# light.net
KiCad netlist of a schematic drawn in Altium Designer
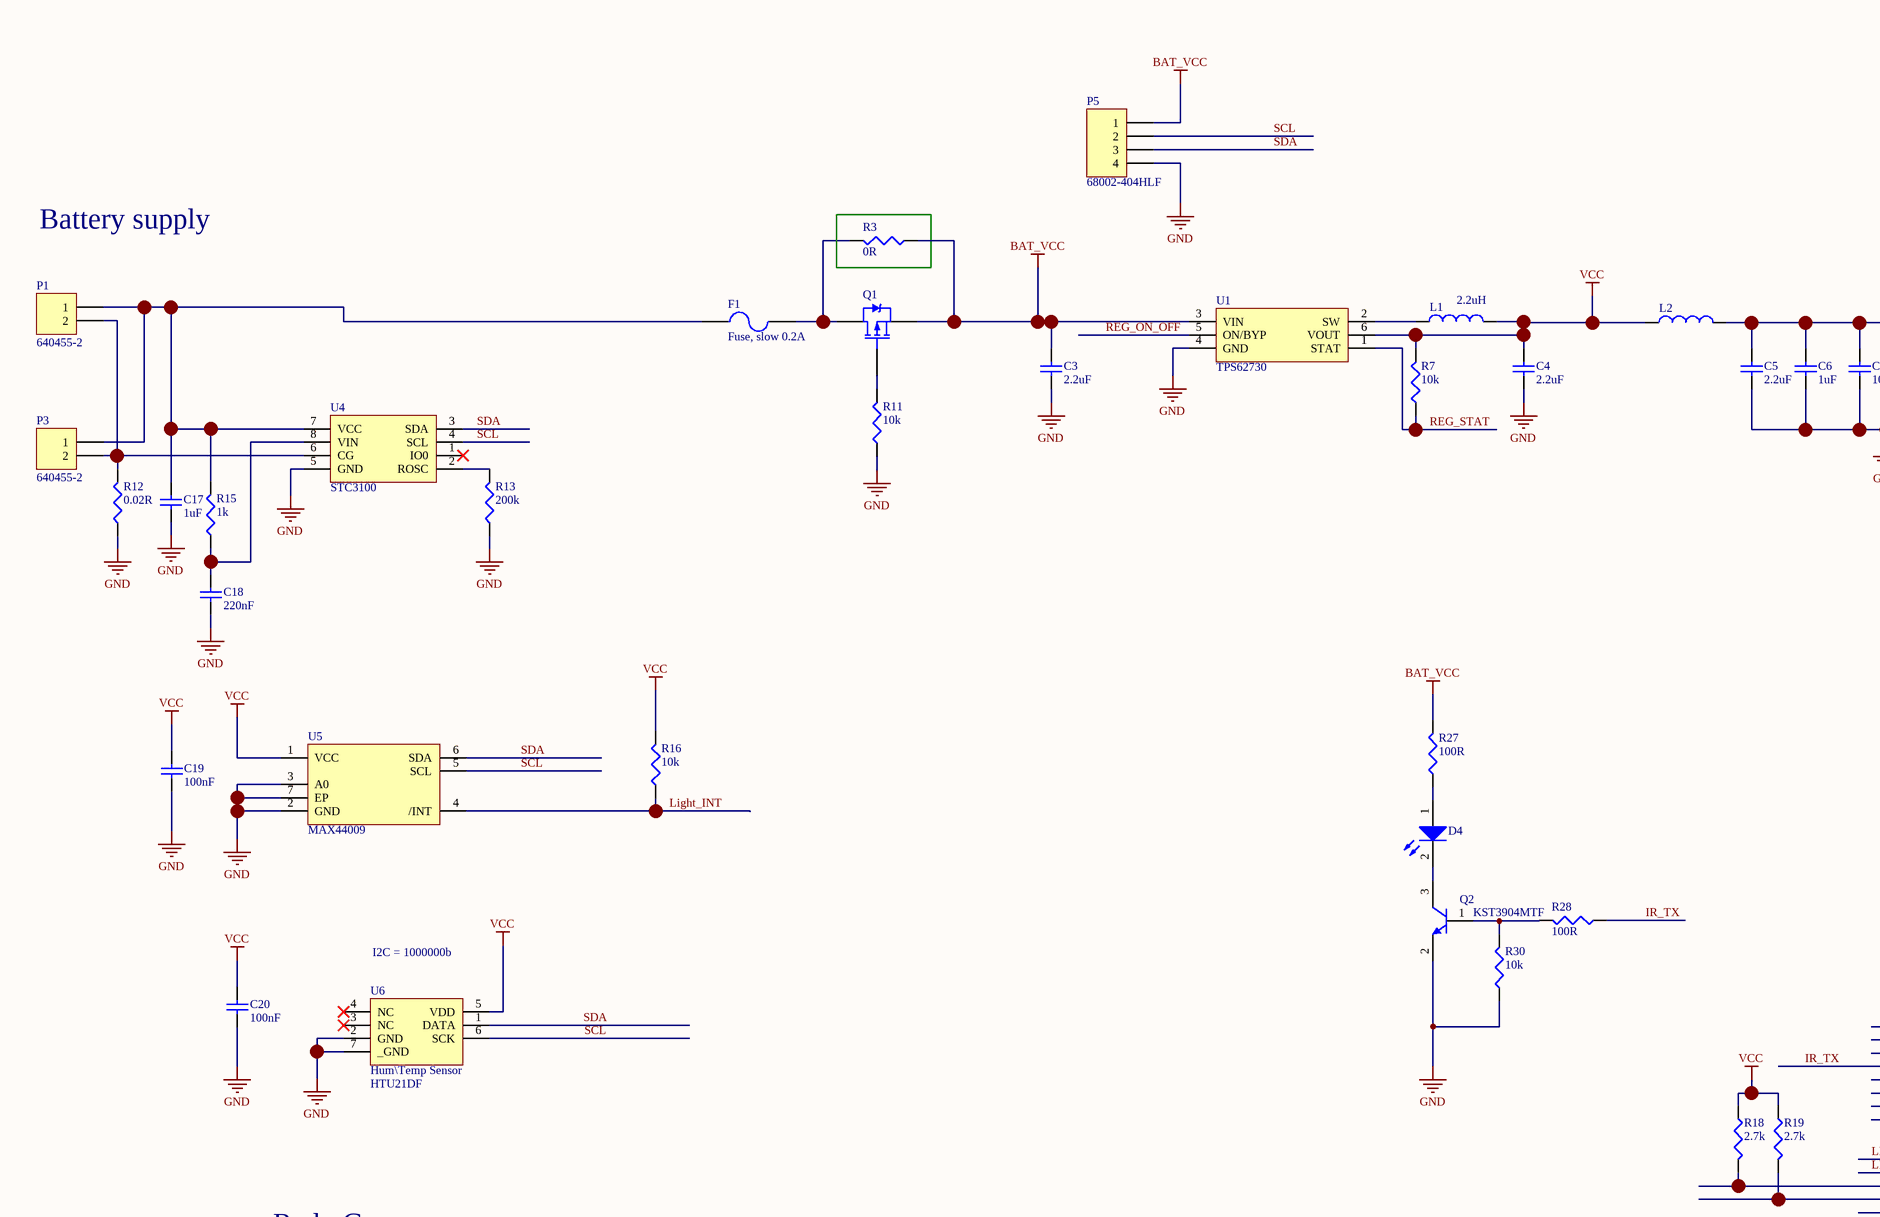
[diagram p0: light.SchDoc, top left]
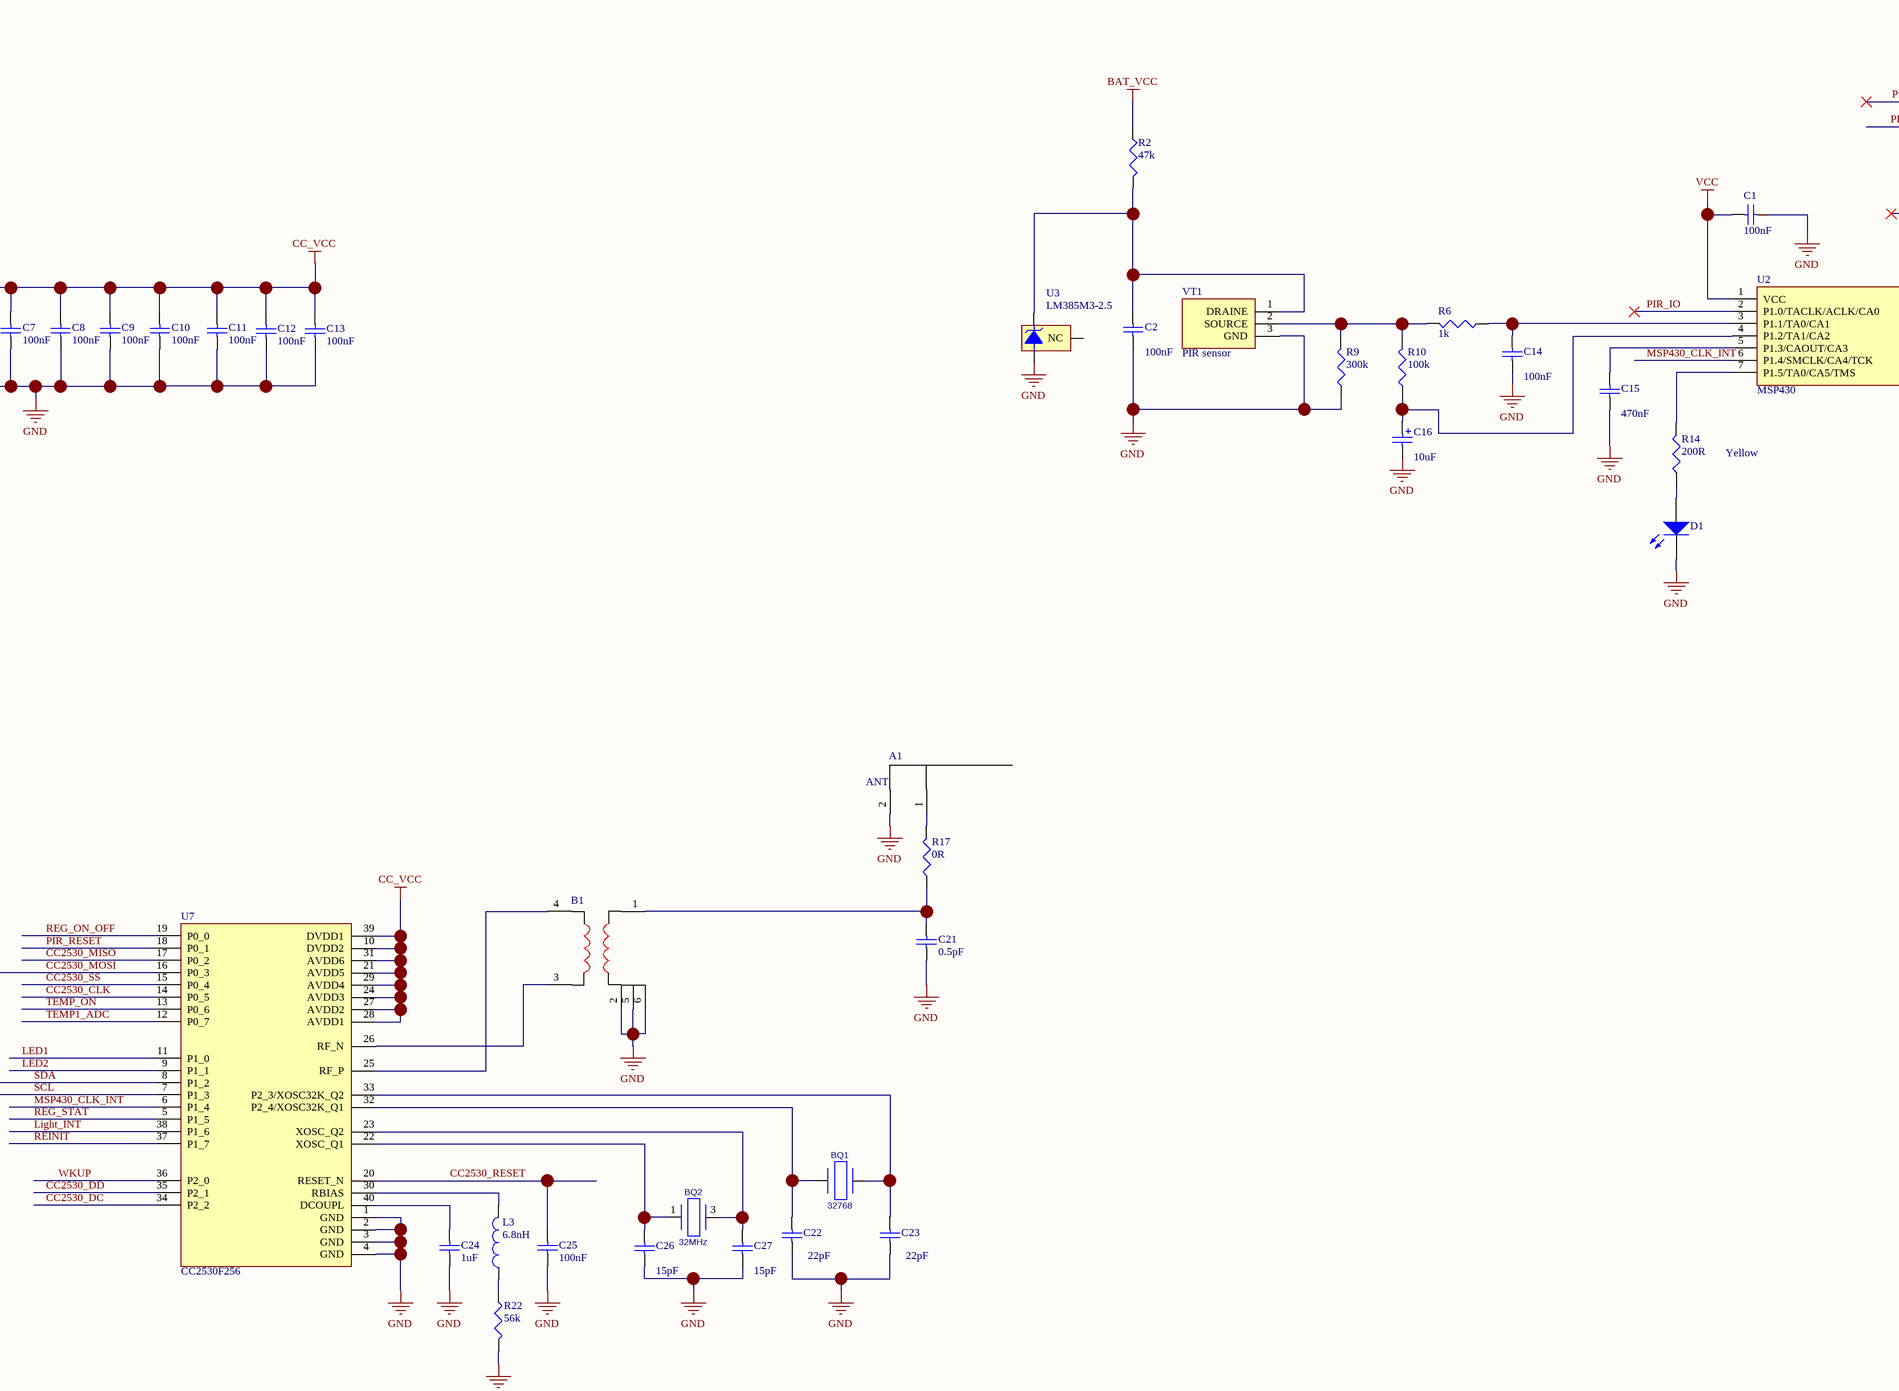
[diagram p1: light.SchDoc, top middle]
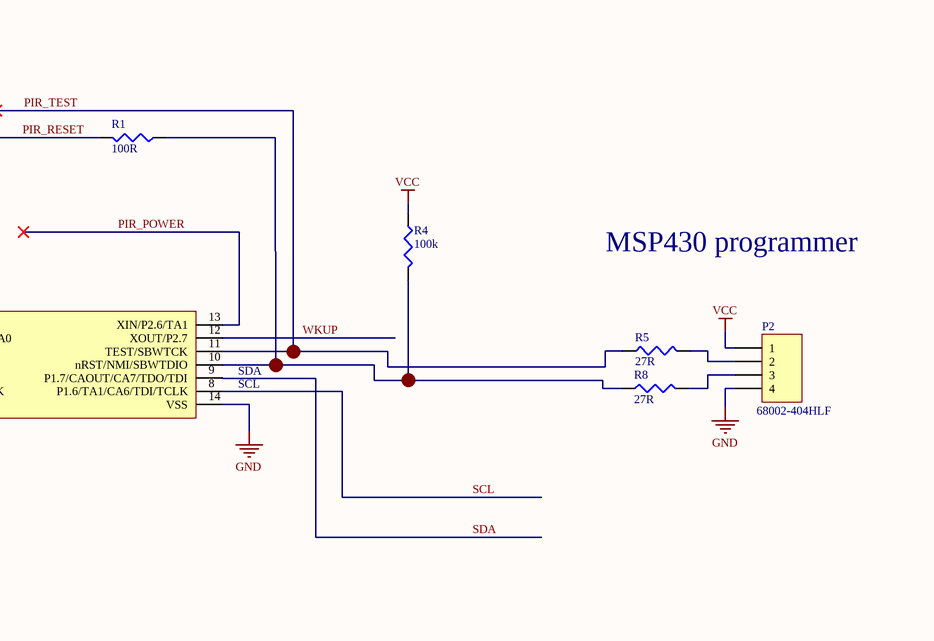
[diagram p2: light.SchDoc, top right]
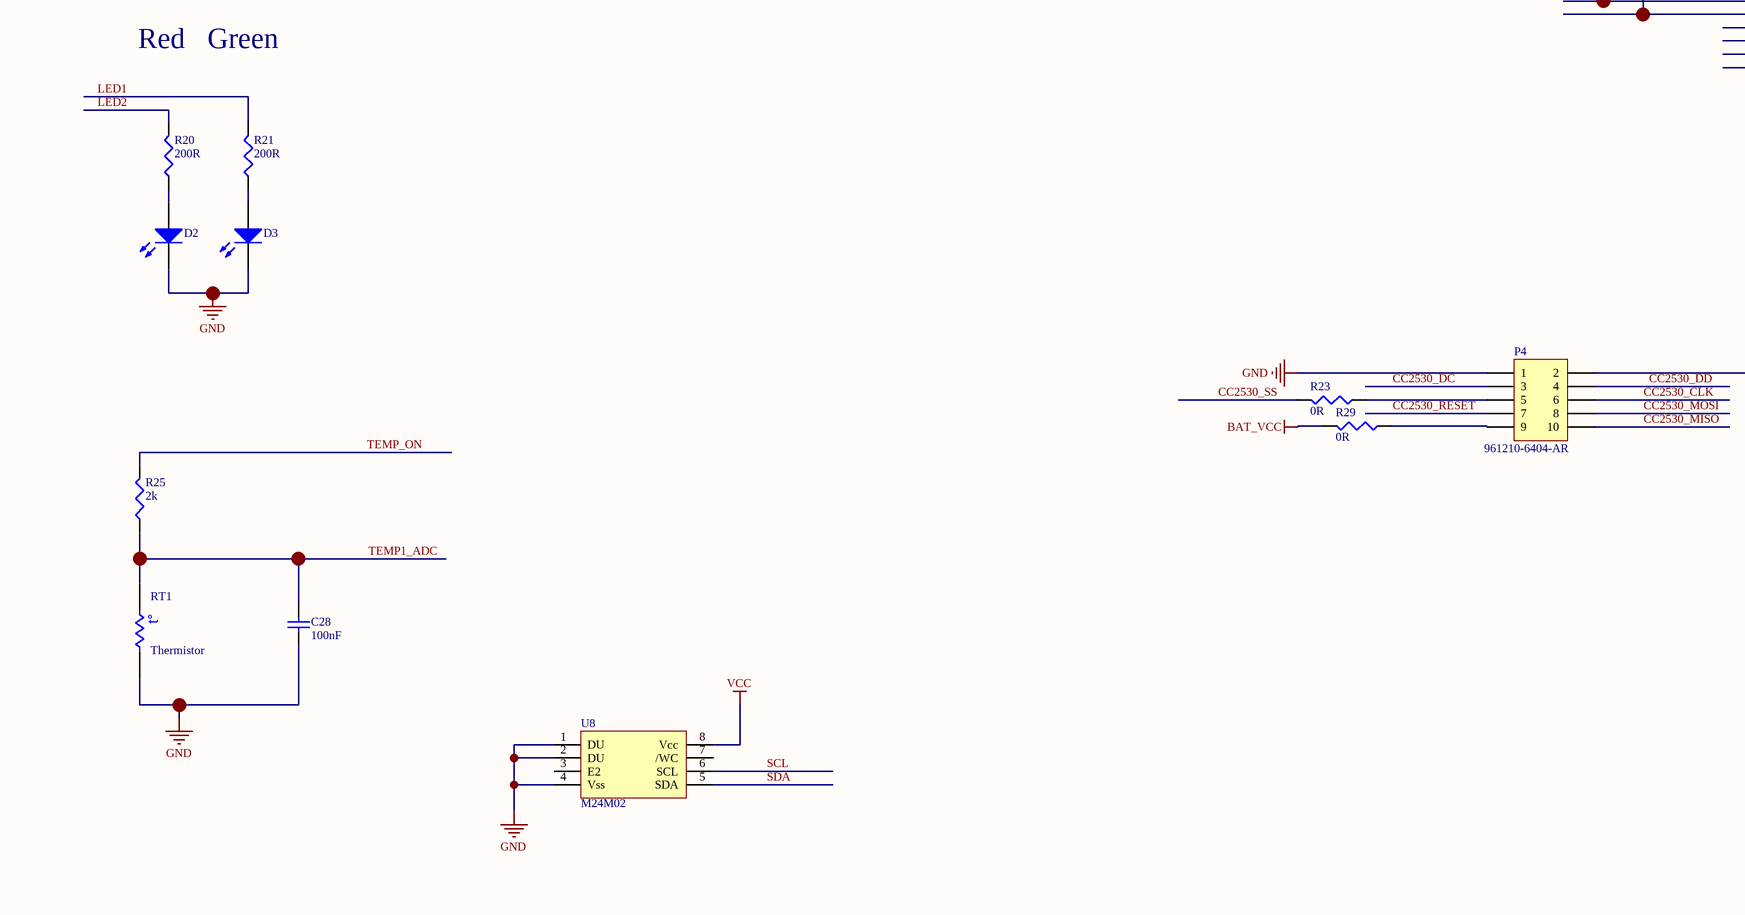
[diagram p3: light.SchDoc, bottom left]
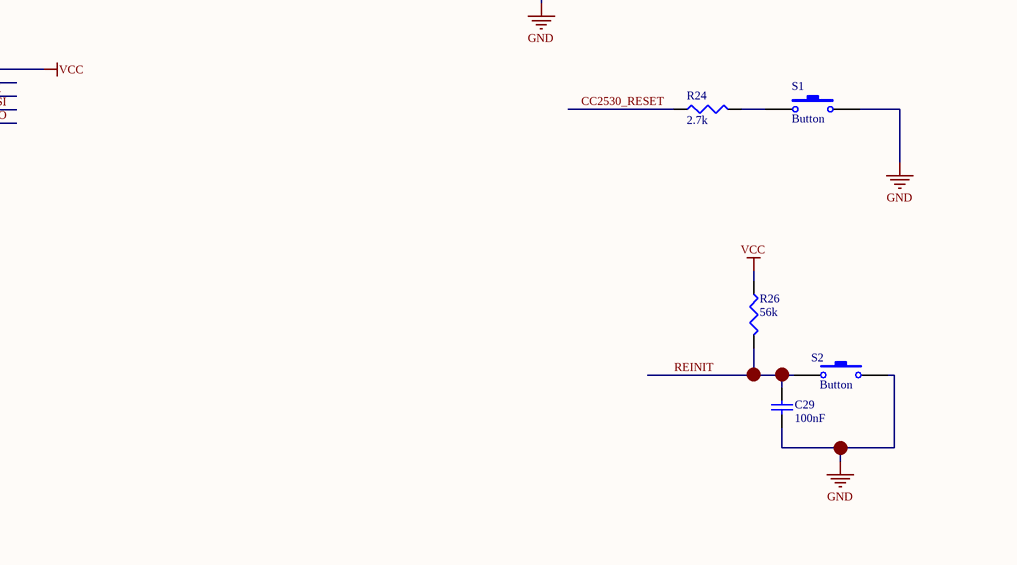
[diagram p4: light.SchDoc, bottom middle]
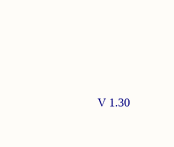
[diagram p5: light.SchDoc, bottom right]

(export (version "E")
  (design (tool "Eeschema 10.0.6"))
  (components
    (comp (ref "A1")
      (value "ANT")
      (footprint "F ant")
      (description "Inverted-F Antenna")
      (fields (field (name "MANUFACTURER PART NUMBER") "PCB ANT"))
      (libsource (lib "CC25xx") (part "ANT"))
    )
    (comp (ref "B1")
      (value "BALUN")
      (footprint "2450BM15A0002")
      (description "BALUN JTI MATCHED ZIGBEE")
      (fields
        (field (name "MANUFACTURER PART NUMBER") "2450BM15A0002E")
        (field (name "MANUFACTURER") "Johanson Technology Inc")
      )
      (libsource (lib "CC25xx") (part "BALUN"))
    )
    (comp (ref "BQ1")
      (value "32768")
      (footprint "FC-12M")
      (description "CRYSTAL 32.768KHZ 12.5PF SMD")
      (fields
        (field (name "MANUFACTURER PART NUMBER") "FC-12M 32.7680KA-A3")
        (field (name "MANUFACTURER") "EPSON")
      )
      (libsource (lib "*") (part "6LC{colon}308C"))
    )
    (comp (ref "BQ2")
      (value "32MHz")
      (footprint "403C11A32M00000")
      (description "CRYSTAL 32MHZ 10PF SMD")
      (fields
        (field (name "MANUFACTURER PART NUMBER") "403C11A32M00000")
        (field (name "MANUFACTURER") "CTS-Frequency Controls")
      )
      (libsource (lib "*") (part "HC-49SMD"))
    )
    (comp (ref "C1")
      (value "100nF")
      (footprint "0402")
      (description "CAP CER 0.1UF 10V 20% X5R 0402")
      (fields
        (field (name "MANUFACTURER PART NUMBER") "CL05A104MP5NNNC")
        (field (name "MANUFACTURER") "Samsung Electro-Mechanics America, Inc")
      )
      (libsource (lib "Miscellaneous Devices") (part "Cap"))
    )
    (comp (ref "C2")
      (value "100nF")
      (footprint "6-0805_L")
      (description "CAP FILM 0.1UF 16VDC 0805")
      (fields
        (field (name "MANUFACTURER PART NUMBER") "ECP-U1C104MA5")
        (field (name "MANUFACTURER") "Panasonic Electronic Components")
      )
      (libsource (lib "Miscellaneous Devices") (part "Cap"))
    )
    (comp (ref "C3")
      (value "2.2uF")
      (footprint "0402")
      (description "CAP CER 2.2UF 6.3V 20% X5R 0402")
      (fields
        (field (name "MANUFACTURER PART NUMBER") "CL05A225MQ5NNNC")
        (field (name "MANUFACTURER") "Samsung Electro-Mechanics America, Inc")
      )
      (libsource (lib "Miscellaneous Devices") (part "Cap"))
    )
    (comp (ref "C4")
      (value "2.2uF")
      (footprint "0402")
      (description "CAP CER 2.2UF 6.3V 20% X5R 0402")
      (fields
        (field (name "MANUFACTURER PART NUMBER") "CL05A225MQ5NNNC")
        (field (name "MANUFACTURER") "Samsung Electro-Mechanics America, Inc")
      )
      (libsource (lib "Miscellaneous Devices") (part "Cap"))
    )
    (comp (ref "C5")
      (value "2.2uF")
      (footprint "0402")
      (description "CAP CER 2.2UF 6.3V 20% X5R 0402")
      (fields
        (field (name "MANUFACTURER PART NUMBER") "CL05A225MQ5NNNC")
        (field (name "MANUFACTURER") "Samsung Electro-Mechanics America, Inc")
      )
      (libsource (lib "Miscellaneous Devices") (part "Cap"))
    )
    (comp (ref "C6")
      (value "1uF")
      (footprint "0402")
      (description "CAP CER 1UF 6.3V 10% X5R 0402")
      (fields
        (field (name "MANUFACTURER PART NUMBER") "GRM155R60J105KE19D")
        (field (name "MANUFACTURER") "Murata Electronics North America")
      )
      (libsource (lib "Miscellaneous Devices") (part "Cap"))
    )
    (comp (ref "C7")
      (value "100nF")
      (footprint "0402")
      (description "CAP CER 0.1UF 10V 20% X5R 0402")
      (fields
        (field (name "MANUFACTURER PART NUMBER") "CL05A104MP5NNNC")
        (field (name "MANUFACTURER") "Samsung Electro-Mechanics America, Inc")
      )
      (libsource (lib "Miscellaneous Devices") (part "Cap"))
    )
    (comp (ref "C8")
      (value "100nF")
      (footprint "0402")
      (description "CAP CER 0.1UF 10V 20% X5R 0402")
      (fields
        (field (name "MANUFACTURER PART NUMBER") "CL05A104MP5NNNC")
        (field (name "MANUFACTURER") "Samsung Electro-Mechanics America, Inc")
      )
      (libsource (lib "Miscellaneous Devices") (part "Cap"))
    )
    (comp (ref "C9")
      (value "100nF")
      (footprint "0402")
      (description "CAP CER 0.1UF 10V 20% X5R 0402")
      (fields
        (field (name "MANUFACTURER PART NUMBER") "CL05A104MP5NNNC")
        (field (name "MANUFACTURER") "Samsung Electro-Mechanics America, Inc")
      )
      (libsource (lib "Miscellaneous Devices") (part "Cap"))
    )
    (comp (ref "C10")
      (value "100nF")
      (footprint "0402")
      (description "CAP CER 0.1UF 10V 20% X5R 0402")
      (fields
        (field (name "MANUFACTURER PART NUMBER") "CL05A104MP5NNNC")
        (field (name "MANUFACTURER") "Samsung Electro-Mechanics America, Inc")
      )
      (libsource (lib "Miscellaneous Devices") (part "Cap"))
    )
    (comp (ref "C11")
      (value "100nF")
      (footprint "0402")
      (description "CAP CER 0.1UF 10V 20% X5R 0402")
      (fields
        (field (name "MANUFACTURER PART NUMBER") "CL05A104MP5NNNC")
        (field (name "MANUFACTURER") "Samsung Electro-Mechanics America, Inc")
      )
      (libsource (lib "Miscellaneous Devices") (part "Cap"))
    )
    (comp (ref "C12")
      (value "100nF")
      (footprint "0402")
      (description "CAP CER 0.1UF 10V 20% X5R 0402")
      (fields
        (field (name "MANUFACTURER PART NUMBER") "CL05A104MP5NNNC")
        (field (name "MANUFACTURER") "Samsung Electro-Mechanics America, Inc")
      )
      (libsource (lib "Miscellaneous Devices") (part "Cap"))
    )
    (comp (ref "C13")
      (value "100nF")
      (footprint "0402")
      (description "CAP CER 0.1UF 10V 20% X5R 0402")
      (fields
        (field (name "MANUFACTURER PART NUMBER") "CL05A104MP5NNNC")
        (field (name "MANUFACTURER") "Samsung Electro-Mechanics America, Inc")
      )
      (libsource (lib "Miscellaneous Devices") (part "Cap"))
    )
    (comp (ref "C14")
      (value "100nF")
      (footprint "6-0805_L")
      (description "CAP FILM 0.1UF 16VDC 0805")
      (fields
        (field (name "MANUFACTURER PART NUMBER") "ECP-U1C104MA5")
        (field (name "MANUFACTURER") "Panasonic Electronic Components")
      )
      (libsource (lib "Miscellaneous Devices") (part "Cap"))
    )
    (comp (ref "C15")
      (value "470nF")
      (footprint "1206")
      (description "CAP FILM 0.47UF 16VDC 1206")
      (fields
        (field (name "MANUFACTURER PART NUMBER") "ECP-U1C474MA5")
        (field (name "MANUFACTURER") "Panasonic Electronic Components")
      )
      (libsource (lib "Miscellaneous Devices") (part "Cap"))
    )
    (comp (ref "C16")
      (value "10uF")
      (footprint "0603")
      (description "CAP CER 10UF 6.3V 20% X5R 0603")
      (fields
        (field (name "MANUFACTURER PART NUMBER") "GRM188R60J106ME47D")
        (field (name "MANUFACTURER") "Murata Electronics North America")
      )
      (libsource (lib "Miscellaneous Devices") (part "Cap Pol2"))
    )
    (comp (ref "C17")
      (value "1uF")
      (footprint "0402")
      (description "CAP CER 1UF 6.3V 10% X5R 0402")
      (fields
        (field (name "MANUFACTURER PART NUMBER") "GRM155R60J105KE19D")
        (field (name "MANUFACTURER") "Murata Electronics North America")
      )
      (libsource (lib "Miscellaneous Devices") (part "Cap"))
    )
    (comp (ref "C18")
      (value "220nF")
      (footprint "0402")
      (description "CAP CER 0.22UF 10V 10% X5R 0402")
      (fields
        (field (name "MANUFACTURER PART NUMBER") "CL05A224KP5NNNC")
        (field (name "MANUFACTURER") "Samsung Electro-Mechanics America, Inc")
      )
      (libsource (lib "Miscellaneous Devices") (part "Cap"))
    )
    (comp (ref "C19")
      (value "100nF")
      (footprint "0402")
      (description "CAP CER 0.1UF 10V 20% X5R 0402")
      (fields
        (field (name "MANUFACTURER PART NUMBER") "CL05A104MP5NNNC")
        (field (name "MANUFACTURER") "Samsung Electro-Mechanics America, Inc")
      )
      (libsource (lib "Miscellaneous Devices") (part "Cap"))
    )
    (comp (ref "C20")
      (value "100nF")
      (footprint "0402")
      (description "CAP CER 0.1UF 10V 20% X5R 0402")
      (fields
        (field (name "MANUFACTURER PART NUMBER") "CL05A104MP5NNNC")
        (field (name "MANUFACTURER") "Samsung Electro-Mechanics America, Inc")
      )
      (libsource (lib "Miscellaneous Devices") (part "Cap"))
    )
    (comp (ref "C21")
      (value "0.5pF")
      (footprint "0402")
      (description "CAP CER 0.5PF 50V NP0 0402")
      (fields
        (field (name "MANUFACTURER PART NUMBER") "GRM1555C1HR50CA01D")
        (field (name "MANUFACTURER") "Murata Electronics North America")
      )
      (libsource (lib "Miscellaneous Devices") (part "Cap"))
    )
    (comp (ref "C22")
      (value "22pF")
      (footprint "0402")
      (description "CAP CER 22PF 50V 5% NP0 0402")
      (fields
        (field (name "MANUFACTURER PART NUMBER") "GRM1555C1H220JA01D")
        (field (name "MANUFACTURER") "Murata Electronics North America")
      )
      (libsource (lib "Miscellaneous Devices") (part "Cap"))
    )
    (comp (ref "C23")
      (value "22pF")
      (footprint "0402")
      (description "CAP CER 22PF 50V 5% NP0 0402")
      (fields
        (field (name "MANUFACTURER PART NUMBER") "GRM1555C1H220JA01D")
        (field (name "MANUFACTURER") "Murata Electronics North America")
      )
      (libsource (lib "Miscellaneous Devices") (part "Cap"))
    )
    (comp (ref "C24")
      (value "1uF")
      (footprint "0402")
      (description "CAP CER 1UF 6.3V 10% X5R 0402")
      (fields
        (field (name "MANUFACTURER PART NUMBER") "GRM155R60J105KE19D")
        (field (name "MANUFACTURER") "Murata Electronics North America")
      )
      (libsource (lib "Miscellaneous Devices") (part "Cap"))
    )
    (comp (ref "C25")
      (value "100nF")
      (footprint "0402")
      (description "CAP CER 0.1UF 10V 20% X5R 0402")
      (fields
        (field (name "MANUFACTURER PART NUMBER") "CL05A104MP5NNNC")
        (field (name "MANUFACTURER") "Samsung Electro-Mechanics America, Inc")
      )
      (libsource (lib "Miscellaneous Devices") (part "Cap"))
    )
    (comp (ref "C26")
      (value "15pF")
      (footprint "0402")
      (description "CAP CER 15PF 50V 5% NP0 0402")
      (fields
        (field (name "MANUFACTURER PART NUMBER") "GRM1555C1H150JA01D")
        (field (name "MANUFACTURER") "Murata Electronics North America")
      )
      (libsource (lib "Miscellaneous Devices") (part "Cap"))
    )
    (comp (ref "C27")
      (value "15pF")
      (footprint "0402")
      (description "CAP CER 15PF 50V 5% NP0 0402")
      (fields
        (field (name "MANUFACTURER PART NUMBER") "GRM1555C1H150JA01D")
        (field (name "MANUFACTURER") "Murata Electronics North America")
      )
      (libsource (lib "Miscellaneous Devices") (part "Cap"))
    )
    (comp (ref "C28")
      (value "100nF")
      (footprint "0402")
      (description "CAP CER 0.1UF 10V 20% X5R 0402")
      (fields
        (field (name "MANUFACTURER PART NUMBER") "CL05A104MP5NNNC")
        (field (name "MANUFACTURER") "Samsung Electro-Mechanics America, Inc")
      )
      (libsource (lib "Miscellaneous Devices") (part "Cap"))
    )
    (comp (ref "C29")
      (value "100nF")
      (footprint "0402")
      (description "CAP CER 0.1UF 10V 20% X5R 0402")
      (fields
        (field (name "MANUFACTURER PART NUMBER") "CL05A104MP5NNNC")
        (field (name "MANUFACTURER") "Samsung Electro-Mechanics America, Inc")
      )
      (libsource (lib "Miscellaneous Devices") (part "Cap"))
    )
    (comp (ref "D1")
      (value "Led")
      (footprint "LED0603")
      (description "LED YELLOW ROUND CLEAR SMD")
      (fields
        (field (name "MANUFACTURER PART NUMBER") "APTD1608SYCK")
        (field (name "MANUFACTURER") "Kingbright Company LLC")
      )
      (libsource (lib "Miscellaneous Devices") (part "LED0"))
    )
    (comp (ref "D2")
      (value "Led")
      (footprint "LED0603")
      (description "LED RED ROUND CLEAR SMD")
      (fields
        (field (name "MANUFACTURER PART NUMBER") "APTD1608SURCK")
        (field (name "MANUFACTURER") "Kingbright Company LLC")
      )
      (libsource (lib "Miscellaneous Devices") (part "LED0"))
    )
    (comp (ref "D3")
      (value "Led")
      (footprint "LED0603")
      (description "LED GREEN CLEAR THIN 0603 SMD")
      (fields
        (field (name "MANUFACTURER PART NUMBER") "LTST-C191KGKT")
        (field (name "MANUFACTURER") "Lite-On Inc")
      )
      (libsource (lib "Miscellaneous Devices") (part "LED0"))
    )
    (comp (ref "D4")
      (value "Led")
      (footprint "TSHF5410")
      (description "EMITTER IR 5MM HI EFF 940NM")
      (fields
        (field (name "MANUFACTURER PART NUMBER") "TSAL6400")
        (field (name "MANUFACTURER") "Vishay Semiconductor Opto Division")
      )
      (libsource (lib "") (part "LED0_1"))
    )
    (comp (ref "F1")
      (value "Fuse, slow 0.2A")
      (footprint "SF1206S0502")
      (description "FUSE .200A 125V FAST 1206")
      (fields
        (field (name "MANUFACTURER PART NUMBER") "0466.200NR")
        (field (name "MANUFACTURER") "Littelfuse Inc")
      )
      (libsource (lib "Miscellaneous Devices") (part "Fuse 2"))
    )
    (comp (ref "L1")
      (value "2.2uH")
      (footprint "6-0805_L")
      (description "INDUCTOR 2.2UH 0805")
      (fields
        (field (name "MANUFACTURER PART NUMBER") "LQM21PN2R2NGCD")
        (field (name "MANUFACTURER") "Murata Electronics North America")
      )
      (libsource (lib "Miscellaneous Devices") (part "Inductor"))
    )
    (comp (ref "L2")
      (value "Inductor")
      (footprint "0402")
      (description "FILTER CHIP 1000 OHM 250MA 0402")
      (fields
        (field (name "MANUFACTURER PART NUMBER") "BLM15HG102SN1D")
        (field (name "MANUFACTURER") "Murata Electronics North America")
      )
      (libsource (lib "Miscellaneous Devices") (part "Inductor"))
    )
    (comp (ref "L3")
      (value "6.8nH")
      (footprint "0402")
      (description "INDUCTOR 6.8NH 300MA 0402")
      (fields
        (field (name "MANUFACTURER PART NUMBER") "LQG15HS6N8J02D")
        (field (name "MANUFACTURER") "Murata Electronics North America")
      )
      (libsource (lib "Miscellaneous Devices") (part "Inductor"))
    )
    (comp (ref "P1")
      (value "Connector")
      (footprint "BAT_CON")
      (description "CONN HEADER VERT 2POS .100 TIN")
      (fields
        (field (name "MANUFACTURER PART NUMBER") "640455-2")
        (field (name "MANUFACTURER") "TE Connectivity")
      )
      (libsource (lib "Miscellaneous Connectors") (part "Header 2"))
    )
    (comp (ref "P2")
      (value "Header 4")
      (footprint "HDR1X4")
      (description "CONN HEADER 4POS .100 STR TIN")
      (fields (field (name "MANUFACTURER PART NUMBER") "68002-404HLF") (field (name "MANUFACTURER") "FCI"))
      (libsource (lib "") (part "Header 4_1"))
    )
    (comp (ref "P3")
      (value "Connector")
      (footprint "BAT_CON")
      (description "CONN HEADER VERT 2POS .100 TIN")
      (fields
        (field (name "MANUFACTURER PART NUMBER") "640455-2")
        (field (name "MANUFACTURER") "TE Connectivity")
      )
      (libsource (lib "Miscellaneous Connectors") (part "Header 2"))
    )
    (comp (ref "P4")
      (value "*")
      (footprint "HDR2X5")
      (description "CONN HEADER VERT DUAL 10POS GOLD")
      (fields (field (name "MANUFACTURER PART NUMBER") "961210-6404-AR") (field (name "MANUFACTURER") "3M"))
      (libsource (lib "Miscellaneous Connectors") (part "Header 5X2"))
    )
    (comp (ref "P5")
      (value "Header 4")
      (footprint "HDR1X4")
      (description "CONN HEADER 4POS .100 STR TIN")
      (fields (field (name "MANUFACTURER PART NUMBER") "68002-404HLF") (field (name "MANUFACTURER") "FCI"))
      (libsource (lib "Miscellaneous Connectors") (part "Header 4"))
    )
    (comp (ref "Q1")
      (value "IRLML6302GTRPBF")
      (footprint "SOT-23_N")
      (description "HEXFET Power MOSFET")
      (fields
        (field (name "MANUFACTURER") "International Rectifier")
        (field (name "PUBLISHER") "Altium Limited")
      )
      (libsource (lib "IR Discrete MOSFET - Power") (part "IRLML6302"))
    )
    (comp (ref "Q2")
      (value "KST3904MTF")
      (footprint "SOT-23_N")
      (description "TRANSISTOR NPN 40V 200MA SOT-23")
      (fields (field (name "MANUFACTURER") "Fairchild Semiconductor"))
      (libsource (lib "Miscellaneous Devices") (part "2N3904"))
    )
    (comp (ref "R1")
      (value "100R")
      (footprint "0402")
      (description "RES 100 OHM 1/10W 5% 0402 SMD")
      (fields
        (field (name "MANUFACTURER PART NUMBER") "ERJ-2GEJ101X")
        (field (name "MANUFACTURER") "Panasonic Electronic Components")
      )
      (libsource (lib "Miscellaneous Devices") (part "Res3"))
    )
    (comp (ref "R2")
      (value "47k")
      (footprint "0603")
      (description "RES 47K OHM 1/10W 5% 0603 SMD")
      (fields
        (field (name "MANUFACTURER PART NUMBER") "RC0603JR-0747KL")
        (field (name "MANUFACTURER") "Yageo")
      )
      (libsource (lib "Miscellaneous Devices") (part "Res3"))
    )
    (comp (ref "R3")
      (value "0R")
      (footprint "0402")
      (description "RES 0.0 OHM 1/10W JUMP 0402 SMD")
      (fields
        (field (name "MANUFACTURER PART NUMBER") "ERJ-2GE0R00X")
        (field (name "MANUFACTURER") "Panasonic Electronic Components")
      )
      (libsource (lib "Miscellaneous Devices") (part "Res3"))
    )
    (comp (ref "R4")
      (value "100k")
      (footprint "0603")
      (description "RES 100K OHM 1/10W 5% 0603 SMD")
      (fields
        (field (name "MANUFACTURER PART NUMBER") "RC0603JR-07100KL")
        (field (name "MANUFACTURER") "Yageo")
      )
      (libsource (lib "Miscellaneous Devices") (part "Res3"))
    )
    (comp (ref "R5")
      (value "27R")
      (footprint "0603")
      (description "RES 27 OHM 1/10W 5% 0603")
      (fields
        (field (name "MANUFACTURER PART NUMBER") "RC1608J270CS")
        (field (name "MANUFACTURER") "Samsung Electro-Mechanics America, Inc")
      )
      (libsource (lib "Miscellaneous Devices") (part "Res3"))
    )
    (comp (ref "R6")
      (value "1k")
      (footprint "0603")
      (description "RES 1.0K OHM 1/10W 5% 0603 SMD")
      (fields
        (field (name "MANUFACTURER PART NUMBER") "RC0603JR-071KL")
        (field (name "MANUFACTURER") "Yageo")
      )
      (libsource (lib "Miscellaneous Devices") (part "Res3"))
    )
    (comp (ref "R7")
      (value "10k")
      (footprint "0402")
      (description "RES 10K OHM 1/10W 5% 0402 SMD")
      (fields
        (field (name "MANUFACTURER PART NUMBER") "ERJ-2GEJ103X")
        (field (name "MANUFACTURER") "Panasonic Electronic Components")
      )
      (libsource (lib "Miscellaneous Devices") (part "Res3"))
    )
    (comp (ref "R8")
      (value "27R")
      (footprint "0603")
      (description "RES 27 OHM 1/10W 5% 0603")
      (fields
        (field (name "MANUFACTURER PART NUMBER") "RC1608J270CS")
        (field (name "MANUFACTURER") "Samsung Electro-Mechanics America, Inc")
      )
      (libsource (lib "Miscellaneous Devices") (part "Res3"))
    )
    (comp (ref "R9")
      (value "300k")
      (footprint "0603")
      (description "RES 300K OHM 1/10W 5% 0603 SMD")
      (fields
        (field (name "MANUFACTURER PART NUMBER") "RC0603JR-07300KL")
        (field (name "MANUFACTURER") "Yageo")
      )
      (libsource (lib "Miscellaneous Devices") (part "Res3"))
    )
    (comp (ref "R10")
      (value "100k")
      (footprint "0603")
      (description "RES 100K OHM 1/10W 5% 0603 SMD")
      (fields
        (field (name "MANUFACTURER PART NUMBER") "RC0603JR-07100KL")
        (field (name "MANUFACTURER") "Yageo")
      )
      (libsource (lib "Miscellaneous Devices") (part "Res3"))
    )
    (comp (ref "R11")
      (value "10k")
      (footprint "0402")
      (description "RES 10K OHM 1/10W 5% 0402 SMD")
      (fields
        (field (name "MANUFACTURER PART NUMBER") "ERJ-2GEJ103X")
        (field (name "MANUFACTURER") "Panasonic Electronic Components")
      )
      (libsource (lib "Miscellaneous Devices") (part "Res3"))
    )
    (comp (ref "R12")
      (value "0.02R")
      (footprint "0603")
      (description "RES 0.02 OHM 1/4W 1% 0603")
      (fields
        (field (name "MANUFACTURER PART NUMBER") "RU1608FR020CS")
        (field (name "MANUFACTURER") "Samsung Electro-Mechanics America, Inc")
      )
      (libsource (lib "Miscellaneous Devices") (part "Res3"))
    )
    (comp (ref "R13")
      (value "200k")
      (footprint "6-0805_L")
      (description "RES 200K OHM 1/8W .1% 0805 SMD")
      (fields
        (field (name "MANUFACTURER PART NUMBER") "ERA-6AEB204V")
        (field (name "MANUFACTURER") "Panasonic Electronic Components")
      )
      (libsource (lib "Miscellaneous Devices") (part "Res3"))
    )
    (comp (ref "R14")
      (value "200R")
      (footprint "0603")
      (description "RES 200 OHM 1/10W 5% 0603 SMD")
      (fields
        (field (name "MANUFACTURER PART NUMBER") "RC0603JR-07200RL")
        (field (name "MANUFACTURER") "Yageo")
      )
      (libsource (lib "Miscellaneous Devices") (part "Res3"))
    )
    (comp (ref "R15")
      (value "1k")
      (footprint "0402")
      (description "RES 1K OHM 1/10W 1% 0402 SMD")
      (fields
        (field (name "MANUFACTURER PART NUMBER") "ERJ-2RKF1001X")
        (field (name "MANUFACTURER") "Panasonic Electronic Components")
      )
      (libsource (lib "Miscellaneous Devices") (part "Res3"))
    )
    (comp (ref "R16")
      (value "10k")
      (footprint "0402")
      (description "RES 10K OHM 1/10W 5% 0402 SMD")
      (fields
        (field (name "MANUFACTURER PART NUMBER") "ERJ-2GEJ103X")
        (field (name "MANUFACTURER") "Panasonic Electronic Components")
      )
      (libsource (lib "Miscellaneous Devices") (part "Res3"))
    )
    (comp (ref "R17")
      (value "0R")
      (footprint "0402")
      (description "RES 0.0 OHM 1/10W JUMP 0402 SMD")
      (fields
        (field (name "MANUFACTURER PART NUMBER") "ERJ-2GE0R00X")
        (field (name "MANUFACTURER") "Panasonic Electronic Components")
      )
      (libsource (lib "Miscellaneous Devices") (part "Res3"))
    )
    (comp (ref "R18")
      (value "2.7k")
      (footprint "0402")
      (description "RES 2.7K OHM 1/10W 5% 0402 SMD")
      (fields
        (field (name "MANUFACTURER PART NUMBER") "ERJ-2GEJ272X")
        (field (name "MANUFACTURER") "Panasonic Electronic Components")
      )
      (libsource (lib "Miscellaneous Devices") (part "Res3"))
    )
    (comp (ref "R19")
      (value "2.7k")
      (footprint "0402")
      (description "RES 2.7K OHM 1/10W 5% 0402 SMD")
      (fields
        (field (name "MANUFACTURER PART NUMBER") "ERJ-2GEJ272X")
        (field (name "MANUFACTURER") "Panasonic Electronic Components")
      )
      (libsource (lib "Miscellaneous Devices") (part "Res3"))
    )
    (comp (ref "R20")
      (value "200R")
      (footprint "0603")
      (description "RES 200 OHM 1/10W 5% 0603 SMD")
      (fields
        (field (name "MANUFACTURER PART NUMBER") "RC0603JR-07200RL")
        (field (name "MANUFACTURER") "Yageo")
      )
      (libsource (lib "Miscellaneous Devices") (part "Res3"))
    )
    (comp (ref "R21")
      (value "200R")
      (footprint "0603")
      (description "RES 200 OHM 1/10W 5% 0603 SMD")
      (fields
        (field (name "MANUFACTURER PART NUMBER") "RC0603JR-07200RL")
        (field (name "MANUFACTURER") "Yageo")
      )
      (libsource (lib "Miscellaneous Devices") (part "Res3"))
    )
    (comp (ref "R22")
      (value "56k")
      (footprint "0402")
      (description "RES 56K OHM 1/10W 1% 0402 SMD")
      (fields
        (field (name "MANUFACTURER PART NUMBER") "ERJ-2RKF5602X")
        (field (name "MANUFACTURER") "Panasonic Electronic Components")
      )
      (libsource (lib "Miscellaneous Devices") (part "Res3"))
    )
    (comp (ref "R23")
      (value "0R")
      (footprint "0402")
      (description "RES 0.0 OHM 1/10W JUMP 0402 SMD")
      (fields
        (field (name "MANUFACTURER PART NUMBER") "ERJ-2GE0R00X")
        (field (name "MANUFACTURER") "Panasonic Electronic Components")
      )
      (libsource (lib "Miscellaneous Devices") (part "Res3"))
    )
    (comp (ref "R24")
      (value "2.7k")
      (footprint "0402")
      (description "RES 2.7K OHM 1/10W 5% 0402 SMD")
      (fields
        (field (name "MANUFACTURER PART NUMBER") "ERJ-2GEJ272X")
        (field (name "MANUFACTURER") "Panasonic Electronic Components")
      )
      (libsource (lib "Miscellaneous Devices") (part "Res3"))
    )
    (comp (ref "R25")
      (value "2k")
      (footprint "0603")
      (description "RES 2.0K OHM 1/10W 5% 0603 SMD")
      (fields
        (field (name "MANUFACTURER PART NUMBER") "RC0603JR-072KL")
        (field (name "MANUFACTURER") "Yageo")
      )
      (libsource (lib "Miscellaneous Devices") (part "Res3"))
    )
    (comp (ref "R26")
      (value "56k")
      (footprint "0402")
      (description "RES 56K OHM 1/10W 1% 0402 SMD")
      (fields
        (field (name "MANUFACTURER PART NUMBER") "ERJ-2RKF5602X")
        (field (name "MANUFACTURER") "Panasonic Electronic Components")
      )
      (libsource (lib "Miscellaneous Devices") (part "Res3"))
    )
    (comp (ref "R27")
      (value "100R")
      (footprint "0603")
      (description "RES 100 OHM 1/10W 5% 0603 SMD")
      (fields
        (field (name "MANUFACTURER PART NUMBER") "ERJ-3GEYJ101V")
        (field (name "MANUFACTURER") "Panasonic Electronic Components")
      )
      (libsource (lib "Miscellaneous Devices") (part "Res3"))
    )
    (comp (ref "R28")
      (value "100R")
      (footprint "0603")
      (description "RES 100 OHM 1/10W 5% 0603 SMD")
      (fields
        (field (name "MANUFACTURER PART NUMBER") "ERJ-3GEYJ101V")
        (field (name "MANUFACTURER") "Panasonic Electronic Components")
      )
      (libsource (lib "Miscellaneous Devices") (part "Res3"))
    )
    (comp (ref "R29")
      (value "0R")
      (footprint "0402")
      (description "RES 0.0 OHM 1/10W JUMP 0402 SMD")
      (fields
        (field (name "MANUFACTURER PART NUMBER") "ERJ-2GE0R00X")
        (field (name "MANUFACTURER") "Panasonic Electronic Components")
      )
      (libsource (lib "Miscellaneous Devices") (part "Res3"))
    )
    (comp (ref "R30")
      (value "10k")
      (footprint "0402")
      (description "RES 10K OHM 1/10W 5% 0402 SMD")
      (fields
        (field (name "MANUFACTURER PART NUMBER") "ERJ-2GEJ103X")
        (field (name "MANUFACTURER") "Panasonic Electronic Components")
      )
      (libsource (lib "Miscellaneous Devices") (part "Res3"))
    )
    (comp (ref "RT1")
      (value "Thermistor")
      (footprint "0603")
      (description "THERMISTOR NTC 1K OHM 5% 0603")
      (fields
        (field (name "MANUFACTURER PART NUMBER") "ERT-J1VT102J")
        (field (name "MANUFACTURER") "Panasonic Electronic Components")
      )
      (libsource (lib "Miscellaneous Devices") (part "Res Thermal"))
    )
    (comp (ref "S1")
      (value "Button")
      (footprint "B3U-3000P")
      (description "SWITCH TACTILE")
      (fields
        (field (name "MANUFACTURER PART NUMBER") "B3U-1000P")
        (field (name "MANUFACTURER") "Omron Electronics Inc-EMC Div")
      )
      (libsource (lib "Miscellaneous Devices") (part "SW-PB"))
    )
    (comp (ref "S2")
      (value "Button")
      (footprint "TL3330")
      (description "SWITCH TACTILE SPST-NO 0.05A 12V")
      (fields
        (field (name "MANUFACTURER PART NUMBER") "TL3330AF260QG")
        (field (name "MANUFACTURER") "E-Switch")
      )
      (libsource (lib "Miscellaneous Devices") (part "SW-PB"))
    )
    (comp (ref "U1")
      (value "TPS62730")
      (footprint "6SON")
      (description "IC DCDC CONV STP-DN SYNC LP 6SON")
      (fields
        (field (name "MANUFACTURER PART NUMBER") "TPS62730DRYT")
        (field (name "MANUFACTURER") "Texas Instruments")
      )
      (libsource (lib "thermostat_main") (part "TPS62730"))
    )
    (comp (ref "U2")
      (value "MSP430")
      (footprint "TSOP14")
      (description "MIXED SIGNAL MICROCONTROLLER")
      (fields
        (field (name "MANUFACTURER PART NUMBER") "MSP430F2013IPW")
        (field (name "MANUFACTURER") "Texas Instruments")
      )
      (libsource (lib "msp") (part "MSP430F20x3"))
    )
    (comp (ref "U3")
      (value "LM385M3-2.5")
      (footprint "SOT23")
      (description "Micropower Voltage Reference Diode, 3-pin SOT-23")
      (fields
        (field (name "MANUFACTURER") "National Semiconductor")
        (field (name "MANUFACTURER PART NUMBER") "LM385M3-2.5/NOPB")
        (field (name "PUBLISHER") "Altium Limited")
      )
      (libsource (lib "NSC Voltage Reference") (part "LM385M3-2.5"))
    )
    (comp (ref "U4")
      (value "STC3100")
      (footprint "DFN8")
      (description "IC BATTERY MON W/GAUGE 8-DFN")
      (fields
        (field (name "MANUFACTURER PART NUMBER") "STC3100IQT")
        (field (name "MANUFACTURER") "STMicroelectronics")
      )
      (libsource (lib "CC25xx") (part "STC3100"))
    )
    (comp (ref "U5")
      (value "MAX44009")
      (footprint "QFN127P600-8N")
      (description "SENSOR AMBIENT LIGHT 6UTDFN")
      (fields
        (field (name "MANUFACTURER PART NUMBER") "MAX44009EDT+T")
        (field (name "MANUFACTURER") "Maxim Integrated")
      )
      (libsource (lib "thermostat_main") (part "MAX44009"))
    )
    (comp (ref "U6")
      (value "Hu~{m}Temp Sensor")
      (footprint "QFN6")
      (description "Miniature Relative Humidity and Temperature Sensor")
      (fields
        (field (name "MANUFACTURER PART NUMBER") "HTU21DF")
        (field (name "MANUFACTURER") "Measurement Specialties")
      )
      (libsource (lib "HTU21D") (part "HTU21D"))
    )
    (comp (ref "U7")
      (value "CC2530F256")
      (footprint "QFN40")
      (description "IC SOC IEEE 802.15.4/ZIG 40VQFN")
      (fields
        (field (name "MANUFACTURER PART NUMBER") "CC2530F256RHAT")
        (field (name "MANUFACTURER") "Texas Instruments")
      )
      (libsource (lib "CC25xx") (part "CC2530F256"))
    )
    (comp (ref "U8")
      (value "M24M02")
      (footprint "SO8")
      (description "IC EEPROM 2MBIT 1MHZ 8SO")
      (fields
        (field (name "MANUFACTURER PART NUMBER") "M24M02-DRMN6TP")
        (field (name "MANUFACTURER") "STMicroelectronics")
      )
      (libsource (lib "CC25xx") (part "M24M02"))
    )
    (comp (ref "VT1")
      (value "PIR sensor")
      (footprint "TO5")
      (fields (field (name "MANUFACTURER PART NUMBER") "C174") (field (name "MANUFACTURER") "Kube"))
      (libsource (lib "Zilog") (part "PIR_Sensor"))
    )
  )
  (nets
    (net (code "1") (name "/CC2530_CLK") (class "Default")
      (node (ref "P4") (pin "6") (pinfunction "6_6") (pintype "passive"))
      (node (ref "U7") (pin "14") (pinfunction "P0_5_14") (pintype "passive"))
    )
    (net (code "2") (name "/CC2530_DC") (class "Default")
      (node (ref "P4") (pin "3") (pinfunction "3_3") (pintype "passive"))
      (node (ref "U7") (pin "34") (pinfunction "P2_2_34") (pintype "passive"))
    )
    (net (code "3") (name "/CC2530_DD") (class "Default")
      (node (ref "P4") (pin "4") (pinfunction "4_4") (pintype "passive"))
      (node (ref "U7") (pin "35") (pinfunction "P2_1_35") (pintype "passive"))
    )
    (net (code "4") (name "/CC2530_MISO") (class "Default")
      (node (ref "P4") (pin "10") (pinfunction "10_10") (pintype "passive"))
      (node (ref "U7") (pin "17") (pinfunction "P0_2_17") (pintype "passive"))
    )
    (net (code "5") (name "/CC2530_MOSI") (class "Default")
      (node (ref "P4") (pin "8") (pinfunction "8_8") (pintype "passive"))
      (node (ref "R28") (pin "2") (pinfunction "2_2") (pintype "passive"))
      (node (ref "U7") (pin "16") (pinfunction "P0_3_16") (pintype "passive"))
    )
    (net (code "6") (name "/CC2530_RESET") (class "Default")
      (node (ref "C25") (pin "1") (pinfunction "1_1") (pintype "passive"))
      (node (ref "P4") (pin "7") (pinfunction "7_7") (pintype "passive"))
      (node (ref "R24") (pin "2") (pinfunction "2_2") (pintype "passive"))
      (node (ref "U7") (pin "20") (pinfunction "RESET_N_20") (pintype "passive"))
    )
    (net (code "7") (name "/CC2530_SS") (class "Default")
      (node (ref "R23") (pin "2") (pinfunction "2_2") (pintype "passive"))
      (node (ref "U7") (pin "15") (pinfunction "P0_4_15") (pintype "passive"))
    )
    (net (code "8") (name "/LED1") (class "Default")
      (node (ref "R21") (pin "1") (pinfunction "1_1") (pintype "passive"))
      (node (ref "U7") (pin "11") (pinfunction "P1_0_11") (pintype "passive"))
    )
    (net (code "9") (name "/LED2") (class "Default")
      (node (ref "R20") (pin "1") (pinfunction "1_1") (pintype "passive"))
      (node (ref "U7") (pin "9") (pinfunction "P1_1_9") (pintype "passive"))
    )
    (net (code "10") (name "/Light_INT") (class "Default")
      (node (ref "R16") (pin "2") (pinfunction "2_2") (pintype "passive"))
      (node (ref "U5") (pin "4") (pinfunction "/INT_4") (pintype "passive"))
      (node (ref "U7") (pin "38") (pinfunction "P1_6_38") (pintype "passive"))
    )
    (net (code "11") (name "/MSP430_CLK_INT") (class "Default")
      (node (ref "U2") (pin "6") (pinfunction "P1.4/SMCLK/CA4/TCK_6") (pintype "passive"))
      (node (ref "U7") (pin "6") (pinfunction "P1_4_6") (pintype "passive"))
    )
    (net (code "12") (name "/PIR_IO") (class "Default")
      (node (ref "U2") (pin "2") (pinfunction "P1.0/TACLK/ACLK/CA0_2") (pintype "passive+no_connect"))
    )
    (net (code "13") (name "/PIR_POWER") (class "Default")
      (node (ref "U2") (pin "13") (pinfunction "XIN/P2.6/TA1_13") (pintype "passive+no_connect"))
    )
    (net (code "14") (name "/PIR_RESET") (class "Default")
      (node (ref "R1") (pin "2") (pinfunction "2_2") (pintype "passive"))
      (node (ref "U7") (pin "18") (pinfunction "P0_1_18") (pintype "passive"))
    )
    (net (code "15") (name "/PIR_TEST") (class "Default")
      (node (ref "R5") (pin "1") (pinfunction "1_1") (pintype "passive"))
      (node (ref "U2") (pin "11") (pinfunction "TEST/SBWTCK_11") (pintype "passive"))
    )
    (net (code "16") (name "/REG_ON_OFF") (class "Default")
      (node (ref "U1") (pin "5") (pinfunction "ON/BYP_5") (pintype "passive"))
      (node (ref "U7") (pin "19") (pinfunction "P0_0_19") (pintype "passive"))
    )
    (net (code "17") (name "/REG_STAT") (class "Default")
      (node (ref "R7") (pin "2") (pinfunction "2_2") (pintype "passive"))
      (node (ref "U1") (pin "1") (pinfunction "STAT_1") (pintype "passive"))
      (node (ref "U7") (pin "5") (pinfunction "P1_5_5") (pintype "passive"))
    )
    (net (code "18") (name "/REINIT") (class "Default")
      (node (ref "C29") (pin "1") (pinfunction "1_1") (pintype "passive"))
      (node (ref "R26") (pin "2") (pinfunction "2_2") (pintype "passive"))
      (node (ref "S2") (pin "1") (pinfunction "1_1") (pintype "passive"))
      (node (ref "U7") (pin "37") (pinfunction "P1_7_37") (pintype "passive"))
    )
    (net (code "19") (name "/SCL") (class "Default")
      (node (ref "P5") (pin "2") (pinfunction "2_2") (pintype "passive"))
      (node (ref "R19") (pin "1") (pinfunction "1_1") (pintype "passive"))
      (node (ref "U2") (pin "8") (pinfunction "P1.6/TA1/CA6/TDI/TCLK_8") (pintype "passive"))
      (node (ref "U4") (pin "4") (pinfunction "SCL_4") (pintype "passive"))
      (node (ref "U5") (pin "5") (pinfunction "SCL_5") (pintype "passive"))
      (node (ref "U6") (pin "6") (pinfunction "SCK_6") (pintype "passive"))
      (node (ref "U7") (pin "7") (pinfunction "P1_3_7") (pintype "passive"))
      (node (ref "U8") (pin "6") (pinfunction "SCL_6") (pintype "passive"))
    )
    (net (code "20") (name "/SDA") (class "Default")
      (node (ref "P5") (pin "3") (pinfunction "3_3") (pintype "passive"))
      (node (ref "R18") (pin "1") (pinfunction "1_1") (pintype "passive"))
      (node (ref "U2") (pin "9") (pinfunction "P1.7/CAOUT/CA7/TDO/TDI_9") (pintype "passive"))
      (node (ref "U4") (pin "3") (pinfunction "SDA_3") (pintype "passive"))
      (node (ref "U5") (pin "6") (pinfunction "SDA_6") (pintype "passive"))
      (node (ref "U6") (pin "1") (pinfunction "DATA_1") (pintype "passive"))
      (node (ref "U7") (pin "8") (pinfunction "P1_2_8") (pintype "passive"))
      (node (ref "U8") (pin "5") (pinfunction "SDA_5") (pintype "passive"))
    )
    (net (code "21") (name "/TEMP1_ADC") (class "Default")
      (node (ref "C28") (pin "1") (pinfunction "1_1") (pintype "passive"))
      (node (ref "R25") (pin "1") (pinfunction "1_1") (pintype "passive"))
      (node (ref "RT1") (pin "1") (pinfunction "1_1") (pintype "passive"))
      (node (ref "U7") (pin "12") (pinfunction "P0_7_12") (pintype "passive"))
    )
    (net (code "22") (name "/TEMP_ON") (class "Default")
      (node (ref "R25") (pin "2") (pinfunction "2_2") (pintype "passive"))
      (node (ref "U7") (pin "13") (pinfunction "P0_6_13") (pintype "passive"))
    )
    (net (code "23") (name "/WKUP") (class "Default")
      (node (ref "U2") (pin "12") (pinfunction "XOUT/P2.7_12") (pintype "passive"))
      (node (ref "U7") (pin "36") (pinfunction "P2_0_36") (pintype "passive"))
    )
    (net (code "24") (name "BAT_VCC") (class "Default")
      (node (ref "C3") (pin "1") (pinfunction "1_1") (pintype "passive"))
      (node (ref "P5") (pin "1") (pinfunction "1_1") (pintype "passive"))
      (node (ref "Q1") (pin "2") (pinfunction "S_2") (pintype "passive"))
      (node (ref "R2") (pin "2") (pinfunction "2_2") (pintype "passive"))
      (node (ref "R27") (pin "1") (pinfunction "1_1") (pintype "passive"))
      (node (ref "R29") (pin "2") (pinfunction "2_2") (pintype "passive"))
      (node (ref "R3") (pin "1") (pinfunction "1_1") (pintype "passive"))
      (node (ref "U1") (pin "3") (pinfunction "VIN_3") (pintype "passive"))
    )
    (net (code "25") (name "CC_VCC") (class "Default")
      (node (ref "C10") (pin "1") (pinfunction "1_1") (pintype "passive"))
      (node (ref "C11") (pin "1") (pinfunction "1_1") (pintype "passive"))
      (node (ref "C12") (pin "1") (pinfunction "1_1") (pintype "passive"))
      (node (ref "C13") (pin "1") (pinfunction "1_1") (pintype "passive"))
      (node (ref "C5") (pin "1") (pinfunction "1_1") (pintype "passive"))
      (node (ref "C6") (pin "1") (pinfunction "1_1") (pintype "passive"))
      (node (ref "C7") (pin "1") (pinfunction "1_1") (pintype "passive"))
      (node (ref "C8") (pin "1") (pinfunction "1_1") (pintype "passive"))
      (node (ref "C9") (pin "1") (pinfunction "1_1") (pintype "passive"))
      (node (ref "L2") (pin "2") (pinfunction "2_2") (pintype "passive"))
      (node (ref "U7") (pin "10") (pinfunction "DVDD2_10") (pintype "passive"))
      (node (ref "U7") (pin "21") (pinfunction "AVDD5_21") (pintype "passive"))
      (node (ref "U7") (pin "24") (pinfunction "AVDD3_24") (pintype "passive"))
      (node (ref "U7") (pin "27") (pinfunction "AVDD2_27") (pintype "passive"))
      (node (ref "U7") (pin "28") (pinfunction "AVDD1_28") (pintype "passive"))
      (node (ref "U7") (pin "29") (pinfunction "AVDD4_29") (pintype "passive"))
      (node (ref "U7") (pin "31") (pinfunction "AVDD6_31") (pintype "passive"))
      (node (ref "U7") (pin "39") (pinfunction "DVDD1_39") (pintype "passive"))
    )
    (net (code "26") (name "GND") (class "Default")
      (node (ref "A1") (pin "2") (pinfunction "2_2") (pintype "passive"))
      (node (ref "B1") (pin "2") (pinfunction "2_2") (pintype "passive"))
      (node (ref "B1") (pin "5") (pinfunction "5_5") (pintype "passive"))
      (node (ref "B1") (pin "6") (pinfunction "6_6") (pintype "passive"))
      (node (ref "C1") (pin "2") (pinfunction "2_2") (pintype "passive"))
      (node (ref "C10") (pin "2") (pinfunction "2_2") (pintype "passive"))
      (node (ref "C11") (pin "2") (pinfunction "2_2") (pintype "passive"))
      (node (ref "C12") (pin "2") (pinfunction "2_2") (pintype "passive"))
      (node (ref "C13") (pin "2") (pinfunction "2_2") (pintype "passive"))
      (node (ref "C14") (pin "1") (pinfunction "1_1") (pintype "passive"))
      (node (ref "C15") (pin "1") (pinfunction "1_1") (pintype "passive"))
      (node (ref "C16") (pin "2") (pinfunction "2_2") (pintype "passive"))
      (node (ref "C17") (pin "2") (pinfunction "2_2") (pintype "passive"))
      (node (ref "C18") (pin "2") (pinfunction "2_2") (pintype "passive"))
      (node (ref "C19") (pin "2") (pinfunction "2_2") (pintype "passive"))
      (node (ref "C2") (pin "1") (pinfunction "1_1") (pintype "passive"))
      (node (ref "C20") (pin "2") (pinfunction "2_2") (pintype "passive"))
      (node (ref "C21") (pin "2") (pinfunction "2_2") (pintype "passive"))
      (node (ref "C22") (pin "1") (pinfunction "1_1") (pintype "passive"))
      (node (ref "C23") (pin "1") (pinfunction "1_1") (pintype "passive"))
      (node (ref "C24") (pin "2") (pinfunction "2_2") (pintype "passive"))
      (node (ref "C25") (pin "2") (pinfunction "2_2") (pintype "passive"))
      (node (ref "C26") (pin "1") (pinfunction "1_1") (pintype "passive"))
      (node (ref "C27") (pin "1") (pinfunction "1_1") (pintype "passive"))
      (node (ref "C28") (pin "2") (pinfunction "2_2") (pintype "passive"))
      (node (ref "C29") (pin "2") (pinfunction "2_2") (pintype "passive"))
      (node (ref "C3") (pin "2") (pinfunction "2_2") (pintype "passive"))
      (node (ref "C4") (pin "2") (pinfunction "2_2") (pintype "passive"))
      (node (ref "C5") (pin "2") (pinfunction "2_2") (pintype "passive"))
      (node (ref "C6") (pin "2") (pinfunction "2_2") (pintype "passive"))
      (node (ref "C7") (pin "2") (pinfunction "2_2") (pintype "passive"))
      (node (ref "C8") (pin "2") (pinfunction "2_2") (pintype "passive"))
      (node (ref "C9") (pin "2") (pinfunction "2_2") (pintype "passive"))
      (node (ref "D1") (pin "2") (pinfunction "K_2") (pintype "passive"))
      (node (ref "D2") (pin "2") (pinfunction "K_2") (pintype "passive"))
      (node (ref "D3") (pin "2") (pinfunction "K_2") (pintype "passive"))
      (node (ref "P2") (pin "4") (pinfunction "4_4") (pintype "passive"))
      (node (ref "P4") (pin "1") (pinfunction "1_1") (pintype "passive"))
      (node (ref "P5") (pin "4") (pinfunction "4_4") (pintype "passive"))
      (node (ref "Q2") (pin "2") (pinfunction "E_2") (pintype "passive"))
      (node (ref "R11") (pin "2") (pinfunction "2_2") (pintype "passive"))
      (node (ref "R12") (pin "2") (pinfunction "2_2") (pintype "passive"))
      (node (ref "R13") (pin "2") (pinfunction "2_2") (pintype "passive"))
      (node (ref "R22") (pin "2") (pinfunction "2_2") (pintype "passive"))
      (node (ref "R30") (pin "2") (pinfunction "2_2") (pintype "passive"))
      (node (ref "R9") (pin "1") (pinfunction "1_1") (pintype "passive"))
      (node (ref "RT1") (pin "2") (pinfunction "2_2") (pintype "passive"))
      (node (ref "S1") (pin "2") (pinfunction "2_2") (pintype "passive"))
      (node (ref "S2") (pin "2") (pinfunction "2_2") (pintype "passive"))
      (node (ref "U1") (pin "4") (pinfunction "GND_4") (pintype "passive"))
      (node (ref "U2") (pin "14") (pinfunction "VSS_14") (pintype "passive"))
      (node (ref "U3") (pin "2") (pinfunction "-V_2") (pintype "passive"))
      (node (ref "U4") (pin "5") (pinfunction "GND_5") (pintype "passive"))
      (node (ref "U5") (pin "2") (pinfunction "GND_2") (pintype "passive"))
      (node (ref "U5") (pin "3") (pinfunction "A0_3") (pintype "passive"))
      (node (ref "U5") (pin "7") (pinfunction "EP_7") (pintype "passive"))
      (node (ref "U6") (pin "2") (pinfunction "GND_2") (pintype "passive"))
      (node (ref "U6") (pin "7") (pinfunction "_GND_7") (pintype "passive"))
      (node (ref "U7") (pin "1") (pinfunction "GND_1") (pintype "passive"))
      (node (ref "U7") (pin "2") (pinfunction "GND_2") (pintype "passive"))
      (node (ref "U7") (pin "3") (pinfunction "GND_3") (pintype "passive"))
      (node (ref "U7") (pin "4") (pinfunction "GND_4") (pintype "passive"))
      (node (ref "U8") (pin "1") (pinfunction "DU_1") (pintype "passive"))
      (node (ref "U8") (pin "2") (pinfunction "DU_2") (pintype "passive"))
      (node (ref "U8") (pin "4") (pinfunction "Vss_4") (pintype "passive"))
      (node (ref "VT1") (pin "3") (pinfunction "GND_3") (pintype "passive"))
    )
    (net (code "27") (name "Net-(A1-Pad1)") (class "Default")
      (node (ref "A1") (pin "1") (pinfunction "1_1") (pintype "passive"))
      (node (ref "R17") (pin "2") (pinfunction "2_2") (pintype "passive"))
    )
    (net (code "28") (name "Net-(B1-Pad1)") (class "Default")
      (node (ref "B1") (pin "1") (pinfunction "1_1") (pintype "passive"))
      (node (ref "C21") (pin "1") (pinfunction "1_1") (pintype "passive"))
      (node (ref "R17") (pin "1") (pinfunction "1_1") (pintype "passive"))
    )
    (net (code "29") (name "Net-(D1-A)") (class "Default")
      (node (ref "D1") (pin "1") (pinfunction "A_1") (pintype "passive"))
      (node (ref "R14") (pin "2") (pinfunction "2_2") (pintype "passive"))
    )
    (net (code "30") (name "Net-(D2-A)") (class "Default")
      (node (ref "D2") (pin "1") (pinfunction "A_1") (pintype "passive"))
      (node (ref "R20") (pin "2") (pinfunction "2_2") (pintype "passive"))
    )
    (net (code "31") (name "Net-(D3-A)") (class "Default")
      (node (ref "D3") (pin "1") (pinfunction "A_1") (pintype "passive"))
      (node (ref "R21") (pin "2") (pinfunction "2_2") (pintype "passive"))
    )
    (net (code "32") (name "Net-(D4-A)") (class "Default")
      (node (ref "D4") (pin "1") (pinfunction "A_1") (pintype "passive"))
      (node (ref "R27") (pin "2") (pinfunction "2_2") (pintype "passive"))
    )
    (net (code "33") (name "Net-(D4-K)") (class "Default")
      (node (ref "D4") (pin "2") (pinfunction "K_2") (pintype "passive"))
      (node (ref "Q2") (pin "3") (pinfunction "C_3") (pintype "passive"))
    )
    (net (code "34") (name "Net-(L3-Pad1)") (class "Default")
      (node (ref "L3") (pin "1") (pinfunction "1_1") (pintype "passive"))
      (node (ref "R22") (pin "1") (pinfunction "1_1") (pintype "passive"))
    )
    (net (code "35") (name "Net-(P2-Pad2)") (class "Default")
      (node (ref "P2") (pin "2") (pinfunction "2_2") (pintype "passive"))
      (node (ref "R5") (pin "2") (pinfunction "2_2") (pintype "passive"))
    )
    (net (code "36") (name "Net-(P2-Pad3)") (class "Default")
      (node (ref "P2") (pin "3") (pinfunction "3_3") (pintype "passive"))
      (node (ref "R8") (pin "2") (pinfunction "2_2") (pintype "passive"))
    )
    (net (code "37") (name "Net-(P4-Pad5)") (class "Default")
      (node (ref "P4") (pin "5") (pinfunction "5_5") (pintype "passive"))
      (node (ref "R23") (pin "1") (pinfunction "1_1") (pintype "passive"))
    )
    (net (code "38") (name "Net-(P4-Pad9)") (class "Default")
      (node (ref "P4") (pin "9") (pinfunction "9_9") (pintype "passive"))
      (node (ref "R29") (pin "1") (pinfunction "1_1") (pintype "passive"))
    )
    (net (code "39") (name "Net-(Q1-D)") (class "Default")
      (node (ref "F1") (pin "2") (pinfunction "2_2") (pintype "passive"))
      (node (ref "Q1") (pin "3") (pinfunction "D_3") (pintype "passive"))
      (node (ref "R3") (pin "2") (pinfunction "2_2") (pintype "passive"))
    )
    (net (code "40") (name "Net-(Q1-G)") (class "Default")
      (node (ref "Q1") (pin "1") (pinfunction "G_1") (pintype "passive"))
      (node (ref "R11") (pin "1") (pinfunction "1_1") (pintype "passive"))
    )
    (net (code "41") (name "Net-(Q2-B)") (class "Default")
      (node (ref "Q2") (pin "1") (pinfunction "B_1") (pintype "passive"))
      (node (ref "R28") (pin "1") (pinfunction "1_1") (pintype "passive"))
      (node (ref "R30") (pin "1") (pinfunction "1_1") (pintype "passive"))
    )
    (net (code "42") (name "Net-(R24-Pad1)") (class "Default")
      (node (ref "R24") (pin "1") (pinfunction "1_1") (pintype "passive"))
      (node (ref "S1") (pin "1") (pinfunction "1_1") (pintype "passive"))
    )
    (net (code "43") (name "Net-(U1-SW)") (class "Default")
      (node (ref "L1") (pin "1") (pinfunction "1_1") (pintype "passive"))
      (node (ref "U1") (pin "2") (pinfunction "SW_2") (pintype "passive"))
    )
    (net (code "44") (name "Net-(U2-P1.1{slash}TA0{slash}CA1)") (class "Default")
      (node (ref "C14") (pin "2") (pinfunction "2_2") (pintype "passive"))
      (node (ref "R6") (pin "1") (pinfunction "1_1") (pintype "passive"))
      (node (ref "U2") (pin "3") (pinfunction "P1.1/TA0/CA1_3") (pintype "passive"))
    )
    (net (code "45") (name "Net-(U2-P1.2{slash}TA1{slash}CA2)") (class "Default")
      (node (ref "C16") (pin "1") (pinfunction "1_1") (pintype "passive"))
      (node (ref "R10") (pin "1") (pinfunction "1_1") (pintype "passive"))
      (node (ref "U2") (pin "4") (pinfunction "P1.2/TA1/CA2_4") (pintype "passive"))
    )
    (net (code "46") (name "Net-(U2-P1.3{slash}CAOUT{slash}CA3)") (class "Default")
      (node (ref "C15") (pin "2") (pinfunction "2_2") (pintype "passive"))
      (node (ref "U2") (pin "5") (pinfunction "P1.3/CAOUT/CA3_5") (pintype "passive"))
    )
    (net (code "47") (name "Net-(U2-P1.5{slash}TA0{slash}CA5{slash}TMS)") (class "Default")
      (node (ref "R14") (pin "1") (pinfunction "1_1") (pintype "passive"))
      (node (ref "U2") (pin "7") (pinfunction "P1.5/TA0/CA5/TMS_7") (pintype "passive"))
    )
    (net (code "48") (name "Net-(U2-nRST{slash}NMI{slash}SBWTDIO)") (class "Default")
      (node (ref "R1") (pin "1") (pinfunction "1_1") (pintype "passive"))
      (node (ref "R4") (pin "2") (pinfunction "2_2") (pintype "passive"))
      (node (ref "R8") (pin "1") (pinfunction "1_1") (pintype "passive"))
      (node (ref "U2") (pin "10") (pinfunction "nRST/NMI/SBWTDIO_10") (pintype "passive"))
    )
    (net (code "49") (name "Net-(U3-+V)") (class "Default")
      (node (ref "C2") (pin "2") (pinfunction "2_2") (pintype "passive"))
      (node (ref "R2") (pin "1") (pinfunction "1_1") (pintype "passive"))
      (node (ref "U3") (pin "1") (pinfunction "+V_1") (pintype "passive"))
      (node (ref "VT1") (pin "1") (pinfunction "DRAINE_1") (pintype "passive"))
    )
    (net (code "50") (name "Net-(U4-CG)") (class "Default")
      (node (ref "P1") (pin "2") (pinfunction "2_2") (pintype "passive"))
      (node (ref "P3") (pin "2") (pinfunction "2_2") (pintype "passive"))
      (node (ref "R12") (pin "1") (pinfunction "1_1") (pintype "passive"))
      (node (ref "U4") (pin "6") (pinfunction "CG_6") (pintype "passive"))
    )
    (net (code "51") (name "Net-(U4-ROSC)") (class "Default")
      (node (ref "R13") (pin "1") (pinfunction "1_1") (pintype "passive"))
      (node (ref "U4") (pin "2") (pinfunction "ROSC_2") (pintype "passive"))
    )
    (net (code "52") (name "Net-(U4-VCC)") (class "Default")
      (node (ref "C17") (pin "1") (pinfunction "1_1") (pintype "passive"))
      (node (ref "F1") (pin "1") (pinfunction "1_1") (pintype "passive"))
      (node (ref "P1") (pin "1") (pinfunction "1_1") (pintype "passive"))
      (node (ref "P3") (pin "1") (pinfunction "1_1") (pintype "passive"))
      (node (ref "R15") (pin "1") (pinfunction "1_1") (pintype "passive"))
      (node (ref "U4") (pin "7") (pinfunction "VCC_7") (pintype "passive"))
    )
    (net (code "53") (name "Net-(U4-VIN)") (class "Default")
      (node (ref "C18") (pin "1") (pinfunction "1_1") (pintype "passive"))
      (node (ref "R15") (pin "2") (pinfunction "2_2") (pintype "passive"))
      (node (ref "U4") (pin "8") (pinfunction "VIN_8") (pintype "passive"))
    )
    (net (code "54") (name "Net-(U7-DCOUPL)") (class "Default")
      (node (ref "C24") (pin "1") (pinfunction "1_1") (pintype "passive"))
      (node (ref "U7") (pin "40") (pinfunction "DCOUPL_40") (pintype "passive"))
    )
    (net (code "55") (name "Net-(U7-P2_3{slash}XOSC32K_Q2)") (class "Default")
      (node (ref "BQ1") (pin "2") (pintype "passive"))
      (node (ref "C23") (pin "2") (pinfunction "2_2") (pintype "passive"))
      (node (ref "U7") (pin "33") (pinfunction "P2_3/XOSC32K_Q2_33") (pintype "passive"))
    )
    (net (code "56") (name "Net-(U7-P2_4{slash}XOSC32K_Q1)") (class "Default")
      (node (ref "BQ1") (pin "1") (pintype "passive"))
      (node (ref "C22") (pin "2") (pinfunction "2_2") (pintype "passive"))
      (node (ref "U7") (pin "32") (pinfunction "P2_4/XOSC32K_Q1_32") (pintype "passive"))
    )
    (net (code "57") (name "Net-(U7-RBIAS)") (class "Default")
      (node (ref "L3") (pin "2") (pinfunction "2_2") (pintype "passive"))
      (node (ref "U7") (pin "30") (pinfunction "RBIAS_30") (pintype "passive"))
    )
    (net (code "58") (name "Net-(U7-RF_N)") (class "Default")
      (node (ref "B1") (pin "3") (pinfunction "3_3") (pintype "passive"))
      (node (ref "U7") (pin "26") (pinfunction "RF_N_26") (pintype "passive"))
    )
    (net (code "59") (name "Net-(U7-RF_P)") (class "Default")
      (node (ref "B1") (pin "4") (pinfunction "4_4") (pintype "passive"))
      (node (ref "U7") (pin "25") (pinfunction "RF_P_25") (pintype "passive"))
    )
    (net (code "60") (name "Net-(U7-XOSC_Q1)") (class "Default")
      (node (ref "BQ2") (pin "1") (pintype "passive"))
      (node (ref "C26") (pin "2") (pinfunction "2_2") (pintype "passive"))
      (node (ref "U7") (pin "22") (pinfunction "XOSC_Q1_22") (pintype "passive"))
    )
    (net (code "61") (name "Net-(U7-XOSC_Q2)") (class "Default")
      (node (ref "BQ2") (pin "3") (pintype "passive"))
      (node (ref "C27") (pin "2") (pinfunction "2_2") (pintype "passive"))
      (node (ref "U7") (pin "23") (pinfunction "XOSC_Q2_23") (pintype "passive"))
    )
    (net (code "62") (name "Net-(VT1-SOURCE)") (class "Default")
      (node (ref "R10") (pin "2") (pinfunction "2_2") (pintype "passive"))
      (node (ref "R6") (pin "2") (pinfunction "2_2") (pintype "passive"))
      (node (ref "R9") (pin "2") (pinfunction "2_2") (pintype "passive"))
      (node (ref "VT1") (pin "2") (pinfunction "SOURCE_2") (pintype "passive"))
    )
    (net (code "63") (name "VCC") (class "Default")
      (node (ref "C1") (pin "1") (pinfunction "1_1") (pintype "passive"))
      (node (ref "C19") (pin "1") (pinfunction "1_1") (pintype "passive"))
      (node (ref "C20") (pin "1") (pinfunction "1_1") (pintype "passive"))
      (node (ref "C4") (pin "1") (pinfunction "1_1") (pintype "passive"))
      (node (ref "L1") (pin "2") (pinfunction "2_2") (pintype "passive"))
      (node (ref "L2") (pin "1") (pinfunction "1_1") (pintype "passive"))
      (node (ref "P2") (pin "1") (pinfunction "1_1") (pintype "passive"))
      (node (ref "P4") (pin "2") (pinfunction "2_2") (pintype "passive"))
      (node (ref "R16") (pin "1") (pinfunction "1_1") (pintype "passive"))
      (node (ref "R18") (pin "2") (pinfunction "2_2") (pintype "passive"))
      (node (ref "R19") (pin "2") (pinfunction "2_2") (pintype "passive"))
      (node (ref "R26") (pin "1") (pinfunction "1_1") (pintype "passive"))
      (node (ref "R4") (pin "1") (pinfunction "1_1") (pintype "passive"))
      (node (ref "R7") (pin "1") (pinfunction "1_1") (pintype "passive"))
      (node (ref "U1") (pin "6") (pinfunction "VOUT_6") (pintype "passive"))
      (node (ref "U2") (pin "1") (pinfunction "VCC_1") (pintype "passive"))
      (node (ref "U5") (pin "1") (pinfunction "VCC_1") (pintype "passive"))
      (node (ref "U6") (pin "5") (pinfunction "VDD_5") (pintype "passive"))
      (node (ref "U8") (pin "8") (pinfunction "Vcc_8") (pintype "passive"))
    )
    (net (code "64") (name "unconnected-(U3-NC-Pad3)") (class "Default")
      (node (ref "U3") (pin "3") (pinfunction "NC_3") (pintype "passive"))
    )
    (net (code "65") (name "unconnected-(U4-IO0-Pad1)") (class "Default")
      (node (ref "U4") (pin "1") (pinfunction "IO0_1") (pintype "passive+no_connect"))
    )
    (net (code "66") (name "unconnected-(U6-NC-Pad3)") (class "Default")
      (node (ref "U6") (pin "3") (pinfunction "NC_3") (pintype "passive+no_connect"))
    )
    (net (code "67") (name "unconnected-(U6-NC-Pad4)") (class "Default")
      (node (ref "U6") (pin "4") (pinfunction "NC_4") (pintype "passive+no_connect"))
    )
    (net (code "68") (name "unconnected-(U8-E2-Pad3)") (class "Default")
      (node (ref "U8") (pin "3") (pinfunction "E2_3") (pintype "passive"))
    )
    (net (code "69") (name "unconnected-(U8-{slash}WC-Pad7)") (class "Default")
      (node (ref "U8") (pin "7") (pinfunction "/WC_7") (pintype "passive"))
    )
  )
)
